# schematics.net
KiCad netlist of a schematic drawn in Altium Designer
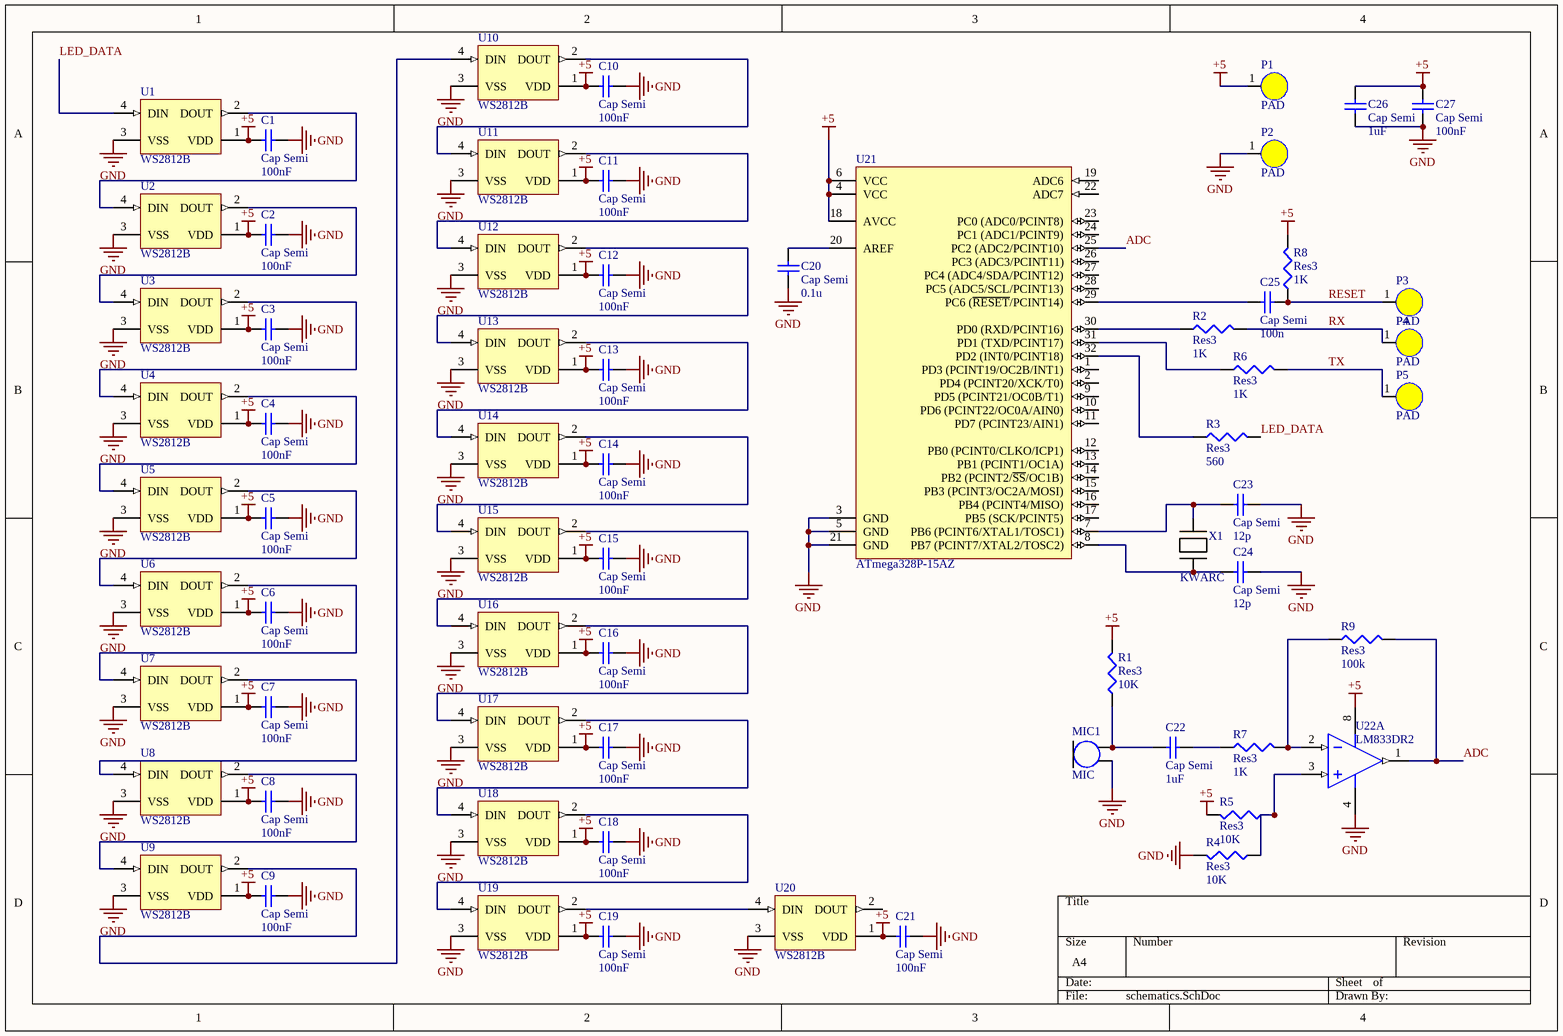
[diagram p0: schematics.SchDoc]

(export (version "E")
  (design (tool "Eeschema 10.0.6"))
  (components
    (comp (ref "C1")
      (value "Cap Semi")
      (footprint "1608[0603]")
      (description "Capacitor (Semiconductor SIM Model)")
      (fields (field (name "ALTIUM_VALUE") "100nF") (field (name "PUBLISHER") "Altium Limited"))
      (libsource (lib "Miscellaneous Devices") (part "Cap Semi"))
    )
    (comp (ref "C2")
      (value "Cap Semi")
      (footprint "1608[0603]")
      (description "Capacitor (Semiconductor SIM Model)")
      (fields (field (name "ALTIUM_VALUE") "100nF") (field (name "PUBLISHER") "Altium Limited"))
      (libsource (lib "Miscellaneous Devices") (part "Cap Semi"))
    )
    (comp (ref "C3")
      (value "Cap Semi")
      (footprint "1608[0603]")
      (description "Capacitor (Semiconductor SIM Model)")
      (fields (field (name "ALTIUM_VALUE") "100nF") (field (name "PUBLISHER") "Altium Limited"))
      (libsource (lib "Miscellaneous Devices") (part "Cap Semi"))
    )
    (comp (ref "C4")
      (value "Cap Semi")
      (footprint "1608[0603]")
      (description "Capacitor (Semiconductor SIM Model)")
      (fields (field (name "ALTIUM_VALUE") "100nF") (field (name "PUBLISHER") "Altium Limited"))
      (libsource (lib "Miscellaneous Devices") (part "Cap Semi"))
    )
    (comp (ref "C5")
      (value "Cap Semi")
      (footprint "1608[0603]")
      (description "Capacitor (Semiconductor SIM Model)")
      (fields (field (name "ALTIUM_VALUE") "100nF") (field (name "PUBLISHER") "Altium Limited"))
      (libsource (lib "Miscellaneous Devices") (part "Cap Semi"))
    )
    (comp (ref "C6")
      (value "Cap Semi")
      (footprint "1608[0603]")
      (description "Capacitor (Semiconductor SIM Model)")
      (fields (field (name "ALTIUM_VALUE") "100nF") (field (name "PUBLISHER") "Altium Limited"))
      (libsource (lib "Miscellaneous Devices") (part "Cap Semi"))
    )
    (comp (ref "C7")
      (value "Cap Semi")
      (footprint "1608[0603]")
      (description "Capacitor (Semiconductor SIM Model)")
      (fields (field (name "ALTIUM_VALUE") "100nF") (field (name "PUBLISHER") "Altium Limited"))
      (libsource (lib "Miscellaneous Devices") (part "Cap Semi"))
    )
    (comp (ref "C8")
      (value "Cap Semi")
      (footprint "1608[0603]")
      (description "Capacitor (Semiconductor SIM Model)")
      (fields (field (name "ALTIUM_VALUE") "100nF") (field (name "PUBLISHER") "Altium Limited"))
      (libsource (lib "Miscellaneous Devices") (part "Cap Semi"))
    )
    (comp (ref "C9")
      (value "Cap Semi")
      (footprint "1608[0603]")
      (description "Capacitor (Semiconductor SIM Model)")
      (fields (field (name "ALTIUM_VALUE") "100nF") (field (name "PUBLISHER") "Altium Limited"))
      (libsource (lib "Miscellaneous Devices") (part "Cap Semi"))
    )
    (comp (ref "C10")
      (value "Cap Semi")
      (footprint "1608[0603]")
      (description "Capacitor (Semiconductor SIM Model)")
      (fields (field (name "ALTIUM_VALUE") "100nF") (field (name "PUBLISHER") "Altium Limited"))
      (libsource (lib "Miscellaneous Devices") (part "Cap Semi"))
    )
    (comp (ref "C11")
      (value "Cap Semi")
      (footprint "1608[0603]")
      (description "Capacitor (Semiconductor SIM Model)")
      (fields (field (name "ALTIUM_VALUE") "100nF") (field (name "PUBLISHER") "Altium Limited"))
      (libsource (lib "Miscellaneous Devices") (part "Cap Semi"))
    )
    (comp (ref "C12")
      (value "Cap Semi")
      (footprint "1608[0603]")
      (description "Capacitor (Semiconductor SIM Model)")
      (fields (field (name "ALTIUM_VALUE") "100nF") (field (name "PUBLISHER") "Altium Limited"))
      (libsource (lib "Miscellaneous Devices") (part "Cap Semi"))
    )
    (comp (ref "C13")
      (value "Cap Semi")
      (footprint "1608[0603]")
      (description "Capacitor (Semiconductor SIM Model)")
      (fields (field (name "ALTIUM_VALUE") "100nF") (field (name "PUBLISHER") "Altium Limited"))
      (libsource (lib "Miscellaneous Devices") (part "Cap Semi"))
    )
    (comp (ref "C14")
      (value "Cap Semi")
      (footprint "1608[0603]")
      (description "Capacitor (Semiconductor SIM Model)")
      (fields (field (name "ALTIUM_VALUE") "100nF") (field (name "PUBLISHER") "Altium Limited"))
      (libsource (lib "Miscellaneous Devices") (part "Cap Semi"))
    )
    (comp (ref "C15")
      (value "Cap Semi")
      (footprint "1608[0603]")
      (description "Capacitor (Semiconductor SIM Model)")
      (fields (field (name "ALTIUM_VALUE") "100nF") (field (name "PUBLISHER") "Altium Limited"))
      (libsource (lib "Miscellaneous Devices") (part "Cap Semi"))
    )
    (comp (ref "C16")
      (value "Cap Semi")
      (footprint "1608[0603]")
      (description "Capacitor (Semiconductor SIM Model)")
      (fields (field (name "ALTIUM_VALUE") "100nF") (field (name "PUBLISHER") "Altium Limited"))
      (libsource (lib "Miscellaneous Devices") (part "Cap Semi"))
    )
    (comp (ref "C17")
      (value "Cap Semi")
      (footprint "1608[0603]")
      (description "Capacitor (Semiconductor SIM Model)")
      (fields (field (name "ALTIUM_VALUE") "100nF") (field (name "PUBLISHER") "Altium Limited"))
      (libsource (lib "Miscellaneous Devices") (part "Cap Semi"))
    )
    (comp (ref "C18")
      (value "Cap Semi")
      (footprint "1608[0603]")
      (description "Capacitor (Semiconductor SIM Model)")
      (fields (field (name "ALTIUM_VALUE") "100nF") (field (name "PUBLISHER") "Altium Limited"))
      (libsource (lib "Miscellaneous Devices") (part "Cap Semi"))
    )
    (comp (ref "C19")
      (value "Cap Semi")
      (footprint "1608[0603]")
      (description "Capacitor (Semiconductor SIM Model)")
      (fields (field (name "ALTIUM_VALUE") "100nF") (field (name "PUBLISHER") "Altium Limited"))
      (libsource (lib "Miscellaneous Devices") (part "Cap Semi"))
    )
    (comp (ref "C20")
      (value "Cap Semi")
      (footprint "1608[0603]")
      (description "Capacitor (Semiconductor SIM Model)")
      (fields (field (name "ALTIUM_VALUE") "0.1u") (field (name "PUBLISHER") "Altium Limited"))
      (libsource (lib "Miscellaneous Devices") (part "Cap Semi"))
    )
    (comp (ref "C21")
      (value "Cap Semi")
      (footprint "1608[0603]")
      (description "Capacitor (Semiconductor SIM Model)")
      (fields (field (name "ALTIUM_VALUE") "100nF") (field (name "PUBLISHER") "Altium Limited"))
      (libsource (lib "Miscellaneous Devices") (part "Cap Semi"))
    )
    (comp (ref "C22")
      (value "Cap Semi")
      (footprint "1608[0603]")
      (description "Capacitor (Semiconductor SIM Model)")
      (fields (field (name "ALTIUM_VALUE") "1uF") (field (name "PUBLISHER") "Altium Limited"))
      (libsource (lib "Miscellaneous Devices") (part "Cap Semi"))
    )
    (comp (ref "C23")
      (value "Cap Semi")
      (footprint "1608[0603]")
      (description "Capacitor (Semiconductor SIM Model)")
      (fields (field (name "ALTIUM_VALUE") "12p") (field (name "PUBLISHER") "Altium Limited"))
      (libsource (lib "Miscellaneous Devices") (part "Cap Semi"))
    )
    (comp (ref "C24")
      (value "Cap Semi")
      (footprint "1608[0603]")
      (description "Capacitor (Semiconductor SIM Model)")
      (fields (field (name "ALTIUM_VALUE") "12p") (field (name "PUBLISHER") "Altium Limited"))
      (libsource (lib "Miscellaneous Devices") (part "Cap Semi"))
    )
    (comp (ref "C25")
      (value "Cap Semi")
      (footprint "1608[0603]")
      (description "Capacitor (Semiconductor SIM Model)")
      (fields (field (name "ALTIUM_VALUE") "100n") (field (name "PUBLISHER") "Altium Limited"))
      (libsource (lib "Miscellaneous Devices") (part "Cap Semi"))
    )
    (comp (ref "C26")
      (value "Cap Semi")
      (footprint "1608[0603]")
      (description "Capacitor (Semiconductor SIM Model)")
      (fields (field (name "ALTIUM_VALUE") "1uF") (field (name "PUBLISHER") "Altium Limited"))
      (libsource (lib "Miscellaneous Devices") (part "Cap Semi"))
    )
    (comp (ref "C27")
      (value "Cap Semi")
      (footprint "C1206")
      (description "Capacitor (Semiconductor SIM Model)")
      (fields (field (name "ALTIUM_VALUE") "100nF") (field (name "PUBLISHER") "Altium Limited"))
      (libsource (lib "Miscellaneous Devices") (part "Cap Semi"))
    )
    (comp (ref "MIC1") (value "MIC") (footprint "MIC") (libsource (lib "sch") (part "MIC")))
    (comp (ref "P1") (value "PAD") (footprint "PAD") (libsource (lib "sch") (part "PAD")))
    (comp (ref "P2") (value "PAD") (footprint "PAD") (libsource (lib "sch") (part "PAD")))
    (comp (ref "P3") (value "PAD") (footprint "PAD") (libsource (lib "sch") (part "PAD")))
    (comp (ref "P4") (value "PAD") (footprint "PAD") (libsource (lib "sch") (part "PAD")))
    (comp (ref "P5") (value "PAD") (footprint "PAD") (libsource (lib "sch") (part "PAD")))
    (comp (ref "R1")
      (value "Res3")
      (footprint "J1-0603")
      (description "Resistor")
      (fields (field (name "ALTIUM_VALUE") "10K") (field (name "PUBLISHER") "Altium Limited"))
      (libsource (lib "Miscellaneous Devices") (part "Res3"))
    )
    (comp (ref "R2")
      (value "Res3")
      (footprint "J1-0603")
      (description "Resistor")
      (fields (field (name "ALTIUM_VALUE") "1K") (field (name "PUBLISHER") "Altium Limited"))
      (libsource (lib "Miscellaneous Devices") (part "Res3"))
    )
    (comp (ref "R3")
      (value "Res3")
      (footprint "J1-0603")
      (description "Resistor")
      (fields (field (name "ALTIUM_VALUE") "560") (field (name "PUBLISHER") "Altium Limited"))
      (libsource (lib "Miscellaneous Devices") (part "Res3"))
    )
    (comp (ref "R4")
      (value "Res3")
      (footprint "J1-0603")
      (description "Resistor")
      (fields (field (name "ALTIUM_VALUE") "10K") (field (name "PUBLISHER") "Altium Limited"))
      (libsource (lib "Miscellaneous Devices") (part "Res3"))
    )
    (comp (ref "R5")
      (value "Res3")
      (footprint "J1-0603")
      (description "Resistor")
      (fields (field (name "ALTIUM_VALUE") "10K") (field (name "PUBLISHER") "Altium Limited"))
      (libsource (lib "Miscellaneous Devices") (part "Res3"))
    )
    (comp (ref "R6")
      (value "Res3")
      (footprint "J1-0603")
      (description "Resistor")
      (fields (field (name "ALTIUM_VALUE") "1K") (field (name "PUBLISHER") "Altium Limited"))
      (libsource (lib "Miscellaneous Devices") (part "Res3"))
    )
    (comp (ref "R7")
      (value "Res3")
      (footprint "J1-0603")
      (description "Resistor")
      (fields (field (name "ALTIUM_VALUE") "1K") (field (name "PUBLISHER") "Altium Limited"))
      (libsource (lib "Miscellaneous Devices") (part "Res3"))
    )
    (comp (ref "R8")
      (value "Res3")
      (footprint "J1-0603")
      (description "Resistor")
      (fields (field (name "ALTIUM_VALUE") "1K") (field (name "PUBLISHER") "Altium Limited"))
      (libsource (lib "Miscellaneous Devices") (part "Res3"))
    )
    (comp (ref "R9")
      (value "Res3")
      (footprint "J1-0603")
      (description "Resistor")
      (fields (field (name "ALTIUM_VALUE") "100k") (field (name "PUBLISHER") "Altium Limited"))
      (libsource (lib "Miscellaneous Devices") (part "Res3"))
    )
    (comp (ref "U1")
      (value "WS2812B")
      (footprint "ADAI-WS2812B_V")
      (fields (field (name "TOLERANCE") "10%"))
      (libsource (lib "Altium Content Vault") (part "ADAI-WS2812B-4"))
    )
    (comp (ref "U2")
      (value "WS2812B")
      (footprint "ADAI-WS2812B_V")
      (fields (field (name "TOLERANCE") "10%"))
      (libsource (lib "Altium Content Vault") (part "ADAI-WS2812B-4"))
    )
    (comp (ref "U3")
      (value "WS2812B")
      (footprint "ADAI-WS2812B_V")
      (fields (field (name "TOLERANCE") "10%"))
      (libsource (lib "Altium Content Vault") (part "ADAI-WS2812B-4"))
    )
    (comp (ref "U4")
      (value "WS2812B")
      (footprint "ADAI-WS2812B_V")
      (fields (field (name "TOLERANCE") "10%"))
      (libsource (lib "Altium Content Vault") (part "ADAI-WS2812B-4"))
    )
    (comp (ref "U5")
      (value "WS2812B")
      (footprint "ADAI-WS2812B_V")
      (fields (field (name "TOLERANCE") "10%"))
      (libsource (lib "Altium Content Vault") (part "ADAI-WS2812B-4"))
    )
    (comp (ref "U6")
      (value "WS2812B")
      (footprint "ADAI-WS2812B_V")
      (fields (field (name "TOLERANCE") "10%"))
      (libsource (lib "Altium Content Vault") (part "ADAI-WS2812B-4"))
    )
    (comp (ref "U7")
      (value "WS2812B")
      (footprint "ADAI-WS2812B_V")
      (fields (field (name "TOLERANCE") "10%"))
      (libsource (lib "Altium Content Vault") (part "ADAI-WS2812B-4"))
    )
    (comp (ref "U8")
      (value "WS2812B")
      (footprint "ADAI-WS2812B_V")
      (fields (field (name "TOLERANCE") "10%"))
      (libsource (lib "Altium Content Vault") (part "ADAI-WS2812B-4"))
    )
    (comp (ref "U9")
      (value "WS2812B")
      (footprint "ADAI-WS2812B_V")
      (fields (field (name "TOLERANCE") "10%"))
      (libsource (lib "Altium Content Vault") (part "ADAI-WS2812B-4"))
    )
    (comp (ref "U10")
      (value "WS2812B")
      (footprint "ADAI-WS2812B_V")
      (fields (field (name "TOLERANCE") "10%"))
      (libsource (lib "Altium Content Vault") (part "ADAI-WS2812B-4"))
    )
    (comp (ref "U11")
      (value "WS2812B")
      (footprint "ADAI-WS2812B_V")
      (fields (field (name "TOLERANCE") "10%"))
      (libsource (lib "Altium Content Vault") (part "ADAI-WS2812B-4"))
    )
    (comp (ref "U12")
      (value "WS2812B")
      (footprint "ADAI-WS2812B_V")
      (fields (field (name "TOLERANCE") "10%"))
      (libsource (lib "Altium Content Vault") (part "ADAI-WS2812B-4"))
    )
    (comp (ref "U13")
      (value "WS2812B")
      (footprint "ADAI-WS2812B_V")
      (fields (field (name "TOLERANCE") "10%"))
      (libsource (lib "Altium Content Vault") (part "ADAI-WS2812B-4"))
    )
    (comp (ref "U14")
      (value "WS2812B")
      (footprint "ADAI-WS2812B_V")
      (fields (field (name "TOLERANCE") "10%"))
      (libsource (lib "Altium Content Vault") (part "ADAI-WS2812B-4"))
    )
    (comp (ref "U15")
      (value "WS2812B")
      (footprint "ADAI-WS2812B_V")
      (fields (field (name "TOLERANCE") "10%"))
      (libsource (lib "Altium Content Vault") (part "ADAI-WS2812B-4"))
    )
    (comp (ref "U16")
      (value "WS2812B")
      (footprint "ADAI-WS2812B_V")
      (fields (field (name "TOLERANCE") "10%"))
      (libsource (lib "Altium Content Vault") (part "ADAI-WS2812B-4"))
    )
    (comp (ref "U17")
      (value "WS2812B")
      (footprint "ADAI-WS2812B_V")
      (fields (field (name "TOLERANCE") "10%"))
      (libsource (lib "Altium Content Vault") (part "ADAI-WS2812B-4"))
    )
    (comp (ref "U18")
      (value "WS2812B")
      (footprint "ADAI-WS2812B_V")
      (fields (field (name "TOLERANCE") "10%"))
      (libsource (lib "Altium Content Vault") (part "ADAI-WS2812B-4"))
    )
    (comp (ref "U19")
      (value "WS2812B")
      (footprint "ADAI-WS2812B_V")
      (fields (field (name "TOLERANCE") "10%"))
      (libsource (lib "Altium Content Vault") (part "ADAI-WS2812B-4"))
    )
    (comp (ref "U20")
      (value "WS2812B")
      (footprint "ADAI-WS2812B_V")
      (fields (field (name "TOLERANCE") "10%"))
      (libsource (lib "Altium Content Vault") (part "ADAI-WS2812B-4"))
    )
    (comp (ref "U21")
      (value "ATmega328P-15AZ")
      (footprint "32MA_M")
      (libsource (lib "Altium Content Vault") (part "MC-8B-ATM48-SQ32"))
    )
    (comp (ref "U22")
      (value "LM833DR2")
      (footprint "ONSC-SOIC-8-751-07_V")
      (description "Low Noise, Audio Dual Operational Amplifier, -40 to 85 degC, 8-Pin SOIC, Tape and Reel")
      (fields (field (name "MANUFACTURER") "On Semiconductor"))
      (libsource (lib "Altium Content Vault") (part "ONSC-LM833_MC3XXXXX_NCV33202-8"))
    )
    (comp (ref "X1") (value "KWARC") (footprint "MIC") (libsource (lib "sch") (part "KWARC")))
  )
  (nets
    (net (code "1") (name "+5") (class "Default")
      (node (ref "C1") (pin "2") (pinfunction "2_2") (pintype "passive"))
      (node (ref "C10") (pin "2") (pinfunction "2_2") (pintype "passive"))
      (node (ref "C11") (pin "2") (pinfunction "2_2") (pintype "passive"))
      (node (ref "C12") (pin "2") (pinfunction "2_2") (pintype "passive"))
      (node (ref "C13") (pin "2") (pinfunction "2_2") (pintype "passive"))
      (node (ref "C14") (pin "2") (pinfunction "2_2") (pintype "passive"))
      (node (ref "C15") (pin "2") (pinfunction "2_2") (pintype "passive"))
      (node (ref "C16") (pin "2") (pinfunction "2_2") (pintype "passive"))
      (node (ref "C17") (pin "2") (pinfunction "2_2") (pintype "passive"))
      (node (ref "C18") (pin "2") (pinfunction "2_2") (pintype "passive"))
      (node (ref "C19") (pin "2") (pinfunction "2_2") (pintype "passive"))
      (node (ref "C2") (pin "2") (pinfunction "2_2") (pintype "passive"))
      (node (ref "C21") (pin "2") (pinfunction "2_2") (pintype "passive"))
      (node (ref "C26") (pin "2") (pinfunction "2_2") (pintype "passive"))
      (node (ref "C27") (pin "1") (pinfunction "1_1") (pintype "passive"))
      (node (ref "C3") (pin "2") (pinfunction "2_2") (pintype "passive"))
      (node (ref "C4") (pin "2") (pinfunction "2_2") (pintype "passive"))
      (node (ref "C5") (pin "2") (pinfunction "2_2") (pintype "passive"))
      (node (ref "C6") (pin "2") (pinfunction "2_2") (pintype "passive"))
      (node (ref "C7") (pin "2") (pinfunction "2_2") (pintype "passive"))
      (node (ref "C8") (pin "2") (pinfunction "2_2") (pintype "passive"))
      (node (ref "C9") (pin "2") (pinfunction "2_2") (pintype "passive"))
      (node (ref "P1") (pin "1") (pintype "passive"))
      (node (ref "R1") (pin "2") (pinfunction "2_2") (pintype "passive"))
      (node (ref "R5") (pin "2") (pinfunction "2_2") (pintype "passive"))
      (node (ref "R8") (pin "2") (pinfunction "2_2") (pintype "passive"))
      (node (ref "U1") (pin "1") (pinfunction "VDD_1") (pintype "power_in"))
      (node (ref "U10") (pin "1") (pinfunction "VDD_1") (pintype "power_in"))
      (node (ref "U11") (pin "1") (pinfunction "VDD_1") (pintype "power_in"))
      (node (ref "U12") (pin "1") (pinfunction "VDD_1") (pintype "power_in"))
      (node (ref "U13") (pin "1") (pinfunction "VDD_1") (pintype "power_in"))
      (node (ref "U14") (pin "1") (pinfunction "VDD_1") (pintype "power_in"))
      (node (ref "U15") (pin "1") (pinfunction "VDD_1") (pintype "power_in"))
      (node (ref "U16") (pin "1") (pinfunction "VDD_1") (pintype "power_in"))
      (node (ref "U17") (pin "1") (pinfunction "VDD_1") (pintype "power_in"))
      (node (ref "U18") (pin "1") (pinfunction "VDD_1") (pintype "power_in"))
      (node (ref "U19") (pin "1") (pinfunction "VDD_1") (pintype "power_in"))
      (node (ref "U2") (pin "1") (pinfunction "VDD_1") (pintype "power_in"))
      (node (ref "U20") (pin "1") (pinfunction "VDD_1") (pintype "power_in"))
      (node (ref "U21") (pin "18") (pinfunction "AVCC_18") (pintype "power_in"))
      (node (ref "U21") (pin "4") (pinfunction "VCC_4") (pintype "power_in"))
      (node (ref "U21") (pin "6") (pinfunction "VCC_6") (pintype "power_in"))
      (node (ref "U22") (pin "8") (pinfunction "VCC_8") (pintype "power_in"))
      (node (ref "U3") (pin "1") (pinfunction "VDD_1") (pintype "power_in"))
      (node (ref "U4") (pin "1") (pinfunction "VDD_1") (pintype "power_in"))
      (node (ref "U5") (pin "1") (pinfunction "VDD_1") (pintype "power_in"))
      (node (ref "U6") (pin "1") (pinfunction "VDD_1") (pintype "power_in"))
      (node (ref "U7") (pin "1") (pinfunction "VDD_1") (pintype "power_in"))
      (node (ref "U8") (pin "1") (pinfunction "VDD_1") (pintype "power_in"))
      (node (ref "U9") (pin "1") (pinfunction "VDD_1") (pintype "power_in"))
    )
    (net (code "2") (name "/ADC") (class "Default")
      (node (ref "R9") (pin "2") (pinfunction "2_2") (pintype "passive"))
      (node (ref "U21") (pin "25") (pinfunction "PC2_(ADC2/PCINT10)_25") (pintype "bidirectional"))
      (node (ref "U22") (pin "1") (pinfunction "OUT1_1") (pintype "output"))
    )
    (net (code "3") (name "/LED_DATA") (class "Default")
      (node (ref "R3") (pin "2") (pinfunction "2_2") (pintype "passive"))
      (node (ref "U1") (pin "4") (pinfunction "DIN_4") (pintype "input"))
    )
    (net (code "4") (name "/RESET") (class "Default")
      (node (ref "C25") (pin "1") (pinfunction "1_1") (pintype "passive"))
      (node (ref "P3") (pin "1") (pintype "passive"))
      (node (ref "R8") (pin "1") (pinfunction "1_1") (pintype "passive"))
    )
    (net (code "5") (name "/RX") (class "Default")
      (node (ref "P4") (pin "1") (pintype "passive"))
      (node (ref "R2") (pin "2") (pinfunction "2_2") (pintype "passive"))
    )
    (net (code "6") (name "/TX") (class "Default")
      (node (ref "P5") (pin "1") (pintype "passive"))
      (node (ref "R6") (pin "2") (pinfunction "2_2") (pintype "passive"))
    )
    (net (code "7") (name "GND") (class "Default")
      (node (ref "C1") (pin "1") (pinfunction "1_1") (pintype "passive"))
      (node (ref "C10") (pin "1") (pinfunction "1_1") (pintype "passive"))
      (node (ref "C11") (pin "1") (pinfunction "1_1") (pintype "passive"))
      (node (ref "C12") (pin "1") (pinfunction "1_1") (pintype "passive"))
      (node (ref "C13") (pin "1") (pinfunction "1_1") (pintype "passive"))
      (node (ref "C14") (pin "1") (pinfunction "1_1") (pintype "passive"))
      (node (ref "C15") (pin "1") (pinfunction "1_1") (pintype "passive"))
      (node (ref "C16") (pin "1") (pinfunction "1_1") (pintype "passive"))
      (node (ref "C17") (pin "1") (pinfunction "1_1") (pintype "passive"))
      (node (ref "C18") (pin "1") (pinfunction "1_1") (pintype "passive"))
      (node (ref "C19") (pin "1") (pinfunction "1_1") (pintype "passive"))
      (node (ref "C2") (pin "1") (pinfunction "1_1") (pintype "passive"))
      (node (ref "C20") (pin "1") (pinfunction "1_1") (pintype "passive"))
      (node (ref "C21") (pin "1") (pinfunction "1_1") (pintype "passive"))
      (node (ref "C23") (pin "1") (pinfunction "1_1") (pintype "passive"))
      (node (ref "C24") (pin "1") (pinfunction "1_1") (pintype "passive"))
      (node (ref "C26") (pin "1") (pinfunction "1_1") (pintype "passive"))
      (node (ref "C27") (pin "2") (pinfunction "2_2") (pintype "passive"))
      (node (ref "C3") (pin "1") (pinfunction "1_1") (pintype "passive"))
      (node (ref "C4") (pin "1") (pinfunction "1_1") (pintype "passive"))
      (node (ref "C5") (pin "1") (pinfunction "1_1") (pintype "passive"))
      (node (ref "C6") (pin "1") (pinfunction "1_1") (pintype "passive"))
      (node (ref "C7") (pin "1") (pinfunction "1_1") (pintype "passive"))
      (node (ref "C8") (pin "1") (pinfunction "1_1") (pintype "passive"))
      (node (ref "C9") (pin "1") (pinfunction "1_1") (pintype "passive"))
      (node (ref "MIC1") (pin "2") (pinfunction "1_2") (pintype "passive"))
      (node (ref "P2") (pin "1") (pintype "passive"))
      (node (ref "R4") (pin "2") (pinfunction "2_2") (pintype "passive"))
      (node (ref "U1") (pin "3") (pinfunction "VSS_3") (pintype "power_in"))
      (node (ref "U10") (pin "3") (pinfunction "VSS_3") (pintype "power_in"))
      (node (ref "U11") (pin "3") (pinfunction "VSS_3") (pintype "power_in"))
      (node (ref "U12") (pin "3") (pinfunction "VSS_3") (pintype "power_in"))
      (node (ref "U13") (pin "3") (pinfunction "VSS_3") (pintype "power_in"))
      (node (ref "U14") (pin "3") (pinfunction "VSS_3") (pintype "power_in"))
      (node (ref "U15") (pin "3") (pinfunction "VSS_3") (pintype "power_in"))
      (node (ref "U16") (pin "3") (pinfunction "VSS_3") (pintype "power_in"))
      (node (ref "U17") (pin "3") (pinfunction "VSS_3") (pintype "power_in"))
      (node (ref "U18") (pin "3") (pinfunction "VSS_3") (pintype "power_in"))
      (node (ref "U19") (pin "3") (pinfunction "VSS_3") (pintype "power_in"))
      (node (ref "U2") (pin "3") (pinfunction "VSS_3") (pintype "power_in"))
      (node (ref "U20") (pin "3") (pinfunction "VSS_3") (pintype "power_in"))
      (node (ref "U21") (pin "21") (pinfunction "GND_21") (pintype "power_in"))
      (node (ref "U21") (pin "3") (pinfunction "GND_3") (pintype "power_in"))
      (node (ref "U21") (pin "5") (pinfunction "GND_5") (pintype "power_in"))
      (node (ref "U22") (pin "4") (pinfunction "VEE_4") (pintype "power_in"))
      (node (ref "U3") (pin "3") (pinfunction "VSS_3") (pintype "power_in"))
      (node (ref "U4") (pin "3") (pinfunction "VSS_3") (pintype "power_in"))
      (node (ref "U5") (pin "3") (pinfunction "VSS_3") (pintype "power_in"))
      (node (ref "U6") (pin "3") (pinfunction "VSS_3") (pintype "power_in"))
      (node (ref "U7") (pin "3") (pinfunction "VSS_3") (pintype "power_in"))
      (node (ref "U8") (pin "3") (pinfunction "VSS_3") (pintype "power_in"))
      (node (ref "U9") (pin "3") (pinfunction "VSS_3") (pintype "power_in"))
    )
    (net (code "8") (name "Net-(C22-Pad1)") (class "Default")
      (node (ref "C22") (pin "1") (pinfunction "1_1") (pintype "passive"))
      (node (ref "R7") (pin "1") (pinfunction "1_1") (pintype "passive"))
    )
    (net (code "9") (name "Net-(MIC1-0)") (class "Default")
      (node (ref "C22") (pin "2") (pinfunction "2_2") (pintype "passive"))
      (node (ref "MIC1") (pin "1") (pinfunction "0_1") (pintype "passive"))
      (node (ref "R1") (pin "1") (pinfunction "1_1") (pintype "passive"))
    )
    (net (code "10") (name "Net-(U1-DOUT)") (class "Default")
      (node (ref "U1") (pin "2") (pinfunction "DOUT_2") (pintype "output"))
      (node (ref "U2") (pin "4") (pinfunction "DIN_4") (pintype "input"))
    )
    (net (code "11") (name "Net-(U2-DOUT)") (class "Default")
      (node (ref "U2") (pin "2") (pinfunction "DOUT_2") (pintype "output"))
      (node (ref "U3") (pin "4") (pinfunction "DIN_4") (pintype "input"))
    )
    (net (code "12") (name "Net-(U3-DOUT)") (class "Default")
      (node (ref "U3") (pin "2") (pinfunction "DOUT_2") (pintype "output"))
      (node (ref "U4") (pin "4") (pinfunction "DIN_4") (pintype "input"))
    )
    (net (code "13") (name "Net-(U4-DOUT)") (class "Default")
      (node (ref "U4") (pin "2") (pinfunction "DOUT_2") (pintype "output"))
      (node (ref "U5") (pin "4") (pinfunction "DIN_4") (pintype "input"))
    )
    (net (code "14") (name "Net-(U5-DOUT)") (class "Default")
      (node (ref "U5") (pin "2") (pinfunction "DOUT_2") (pintype "output"))
      (node (ref "U6") (pin "4") (pinfunction "DIN_4") (pintype "input"))
    )
    (net (code "15") (name "Net-(U6-DOUT)") (class "Default")
      (node (ref "U6") (pin "2") (pinfunction "DOUT_2") (pintype "output"))
      (node (ref "U7") (pin "4") (pinfunction "DIN_4") (pintype "input"))
    )
    (net (code "16") (name "Net-(U7-DOUT)") (class "Default")
      (node (ref "U7") (pin "2") (pinfunction "DOUT_2") (pintype "output"))
      (node (ref "U8") (pin "4") (pinfunction "DIN_4") (pintype "input"))
    )
    (net (code "17") (name "Net-(U8-DOUT)") (class "Default")
      (node (ref "U8") (pin "2") (pinfunction "DOUT_2") (pintype "output"))
      (node (ref "U9") (pin "4") (pinfunction "DIN_4") (pintype "input"))
    )
    (net (code "18") (name "Net-(U10-DIN)") (class "Default")
      (node (ref "U10") (pin "4") (pinfunction "DIN_4") (pintype "input"))
      (node (ref "U9") (pin "2") (pinfunction "DOUT_2") (pintype "output"))
    )
    (net (code "19") (name "Net-(U10-DOUT)") (class "Default")
      (node (ref "U10") (pin "2") (pinfunction "DOUT_2") (pintype "output"))
      (node (ref "U11") (pin "4") (pinfunction "DIN_4") (pintype "input"))
    )
    (net (code "20") (name "Net-(U11-DOUT)") (class "Default")
      (node (ref "U11") (pin "2") (pinfunction "DOUT_2") (pintype "output"))
      (node (ref "U12") (pin "4") (pinfunction "DIN_4") (pintype "input"))
    )
    (net (code "21") (name "Net-(U12-DOUT)") (class "Default")
      (node (ref "U12") (pin "2") (pinfunction "DOUT_2") (pintype "output"))
      (node (ref "U13") (pin "4") (pinfunction "DIN_4") (pintype "input"))
    )
    (net (code "22") (name "Net-(U13-DOUT)") (class "Default")
      (node (ref "U13") (pin "2") (pinfunction "DOUT_2") (pintype "output"))
      (node (ref "U14") (pin "4") (pinfunction "DIN_4") (pintype "input"))
    )
    (net (code "23") (name "Net-(U14-DOUT)") (class "Default")
      (node (ref "U14") (pin "2") (pinfunction "DOUT_2") (pintype "output"))
      (node (ref "U15") (pin "4") (pinfunction "DIN_4") (pintype "input"))
    )
    (net (code "24") (name "Net-(U15-DOUT)") (class "Default")
      (node (ref "U15") (pin "2") (pinfunction "DOUT_2") (pintype "output"))
      (node (ref "U16") (pin "4") (pinfunction "DIN_4") (pintype "input"))
    )
    (net (code "25") (name "Net-(U16-DOUT)") (class "Default")
      (node (ref "U16") (pin "2") (pinfunction "DOUT_2") (pintype "output"))
      (node (ref "U17") (pin "4") (pinfunction "DIN_4") (pintype "input"))
    )
    (net (code "26") (name "Net-(U17-DOUT)") (class "Default")
      (node (ref "U17") (pin "2") (pinfunction "DOUT_2") (pintype "output"))
      (node (ref "U18") (pin "4") (pinfunction "DIN_4") (pintype "input"))
    )
    (net (code "27") (name "Net-(U18-DOUT)") (class "Default")
      (node (ref "U18") (pin "2") (pinfunction "DOUT_2") (pintype "output"))
      (node (ref "U19") (pin "4") (pinfunction "DIN_4") (pintype "input"))
    )
    (net (code "28") (name "Net-(U19-DOUT)") (class "Default")
      (node (ref "U19") (pin "2") (pinfunction "DOUT_2") (pintype "output"))
      (node (ref "U20") (pin "4") (pinfunction "DIN_4") (pintype "input"))
    )
    (net (code "29") (name "Net-(U21-AREF)") (class "Default")
      (node (ref "C20") (pin "2") (pinfunction "2_2") (pintype "passive"))
      (node (ref "U21") (pin "20") (pinfunction "AREF_20") (pintype "passive"))
    )
    (net (code "30") (name "Net-(U21-PB6_(PCINT6{slash}XTAL1{slash}TOSC1))") (class "Default")
      (node (ref "C23") (pin "2") (pinfunction "2_2") (pintype "passive"))
      (node (ref "U21") (pin "7") (pinfunction "PB6_(PCINT6/XTAL1/TOSC1)_7") (pintype "bidirectional"))
      (node (ref "X1") (pin "1") (pinfunction "0_1") (pintype "passive"))
    )
    (net (code "31") (name "Net-(U21-PB7_(PCINT7{slash}XTAL2{slash}TOSC2))") (class "Default")
      (node (ref "C24") (pin "2") (pinfunction "2_2") (pintype "passive"))
      (node (ref "U21") (pin "8") (pinfunction "PB7_(PCINT7/XTAL2/TOSC2)_8") (pintype "bidirectional"))
      (node (ref "X1") (pin "2") (pinfunction "1_2") (pintype "passive"))
    )
    (net (code "32") (name "Net-(U21-PC6_(~{RESET}{slash}PCINT14))") (class "Default")
      (node (ref "C25") (pin "2") (pinfunction "2_2") (pintype "passive"))
      (node (ref "U21") (pin "29") (pinfunction "PC6_(~{RESET}/PCINT14)_29") (pintype "bidirectional"))
    )
    (net (code "33") (name "Net-(U21-PD0_(RXD{slash}PCINT16))") (class "Default")
      (node (ref "R2") (pin "1") (pinfunction "1_1") (pintype "passive"))
      (node (ref "U21") (pin "30") (pinfunction "PD0_(RXD/PCINT16)_30") (pintype "bidirectional"))
    )
    (net (code "34") (name "Net-(U21-PD1_(TXD{slash}PCINT17))") (class "Default")
      (node (ref "R6") (pin "1") (pinfunction "1_1") (pintype "passive"))
      (node (ref "U21") (pin "31") (pinfunction "PD1_(TXD/PCINT17)_31") (pintype "bidirectional"))
    )
    (net (code "35") (name "Net-(U21-PD2_(INT0{slash}PCINT18))") (class "Default")
      (node (ref "R3") (pin "1") (pinfunction "1_1") (pintype "passive"))
      (node (ref "U21") (pin "32") (pinfunction "PD2_(INT0/PCINT18)_32") (pintype "bidirectional"))
    )
    (net (code "36") (name "Net-(U22A-IN1+)") (class "Default")
      (node (ref "R4") (pin "1") (pinfunction "1_1") (pintype "passive"))
      (node (ref "R5") (pin "1") (pinfunction "1_1") (pintype "passive"))
      (node (ref "U22") (pin "3") (pinfunction "IN1+_3") (pintype "input"))
    )
    (net (code "37") (name "Net-(U22A-IN1-)") (class "Default")
      (node (ref "R7") (pin "2") (pinfunction "2_2") (pintype "passive"))
      (node (ref "R9") (pin "1") (pinfunction "1_1") (pintype "passive"))
      (node (ref "U22") (pin "2") (pinfunction "IN1-_2") (pintype "input"))
    )
    (net (code "38") (name "unconnected-(U20-DOUT-Pad2)") (class "Default")
      (node (ref "U20") (pin "2") (pinfunction "DOUT_2") (pintype "output"))
    )
    (net (code "39") (name "unconnected-(U21-ADC6-Pad19)") (class "Default")
      (node (ref "U21") (pin "19") (pinfunction "ADC6_19") (pintype "input"))
    )
    (net (code "40") (name "unconnected-(U21-ADC7-Pad22)") (class "Default")
      (node (ref "U21") (pin "22") (pinfunction "ADC7_22") (pintype "input"))
    )
    (net (code "41") (name "unconnected-(U21-PB0_(PCINT0{slash}CLKO{slash}ICP1)-Pad12)") (class "Default")
      (node (ref "U21") (pin "12") (pinfunction "PB0_(PCINT0/CLKO/ICP1)_12") (pintype "bidirectional"))
    )
    (net (code "42") (name "unconnected-(U21-PB1_(PCINT1{slash}OC1A)-Pad13)") (class "Default")
      (node (ref "U21") (pin "13") (pinfunction "PB1_(PCINT1/OC1A)_13") (pintype "bidirectional"))
    )
    (net (code "43") (name "unconnected-(U21-PB2_(PCINT2{slash}~{SS}{slash}OC1B)-Pad14)") (class "Default")
      (node (ref "U21") (pin "14") (pinfunction "PB2_(PCINT2/~{SS}/OC1B)_14") (pintype "bidirectional"))
    )
    (net (code "44") (name "unconnected-(U21-PB3_(PCINT3{slash}OC2A{slash}MOSI)-Pad15)") (class "Default")
      (node (ref "U21") (pin "15") (pinfunction "PB3_(PCINT3/OC2A/MOSI)_15") (pintype "bidirectional"))
    )
    (net (code "45") (name "unconnected-(U21-PB4_(PCINT4{slash}MISO)-Pad16)") (class "Default")
      (node (ref "U21") (pin "16") (pinfunction "PB4_(PCINT4/MISO)_16") (pintype "bidirectional"))
    )
    (net (code "46") (name "unconnected-(U21-PB5_(SCK{slash}PCINT5)-Pad17)") (class "Default")
      (node (ref "U21") (pin "17") (pinfunction "PB5_(SCK/PCINT5)_17") (pintype "bidirectional"))
    )
    (net (code "47") (name "unconnected-(U21-PC0_(ADC0{slash}PCINT8)-Pad23)") (class "Default")
      (node (ref "U21") (pin "23") (pinfunction "PC0_(ADC0/PCINT8)_23") (pintype "bidirectional"))
    )
    (net (code "48") (name "unconnected-(U21-PC1_(ADC1{slash}PCINT9)-Pad24)") (class "Default")
      (node (ref "U21") (pin "24") (pinfunction "PC1_(ADC1/PCINT9)_24") (pintype "bidirectional"))
    )
    (net (code "49") (name "unconnected-(U21-PC3_(ADC3{slash}PCINT11)-Pad26)") (class "Default")
      (node (ref "U21") (pin "26") (pinfunction "PC3_(ADC3/PCINT11)_26") (pintype "bidirectional"))
    )
    (net (code "50") (name "unconnected-(U21-PC4_(ADC4{slash}SDA{slash}PCINT12)-Pad27)") (class "Default")
      (node (ref "U21") (pin "27") (pinfunction "PC4_(ADC4/SDA/PCINT12)_27") (pintype "bidirectional"))
    )
    (net (code "51") (name "unconnected-(U21-PC5_(ADC5{slash}SCL{slash}PCINT13)-Pad28)") (class "Default")
      (node (ref "U21") (pin "28") (pinfunction "PC5_(ADC5/SCL/PCINT13)_28") (pintype "bidirectional"))
    )
    (net (code "52") (name "unconnected-(U21-PD3_(PCINT19{slash}OC2B{slash}INT1)-Pad1)") (class "Default")
      (node (ref "U21") (pin "1") (pinfunction "PD3_(PCINT19/OC2B/INT1)_1") (pintype "bidirectional"))
    )
    (net (code "53") (name "unconnected-(U21-PD4_(PCINT20{slash}XCK{slash}T0)-Pad2)") (class "Default")
      (node (ref "U21") (pin "2") (pinfunction "PD4_(PCINT20/XCK/T0)_2") (pintype "bidirectional"))
    )
    (net (code "54") (name "unconnected-(U21-PD5_(PCINT21{slash}OC0B{slash}T1)-Pad9)") (class "Default")
      (node (ref "U21") (pin "9") (pinfunction "PD5_(PCINT21/OC0B/T1)_9") (pintype "bidirectional"))
    )
    (net (code "55") (name "unconnected-(U21-PD6_(PCINT22{slash}OC0A{slash}AIN0)-Pad10)") (class "Default")
      (node (ref "U21") (pin "10") (pinfunction "PD6_(PCINT22/OC0A/AIN0)_10") (pintype "bidirectional"))
    )
    (net (code "56") (name "unconnected-(U21-PD7_(PCINT23{slash}AIN1)-Pad11)") (class "Default")
      (node (ref "U21") (pin "11") (pinfunction "PD7_(PCINT23/AIN1)_11") (pintype "bidirectional"))
    )
  )
)
